# ReceiverPCB_trial1.net
KiCad netlist of a schematic drawn in EAGLE
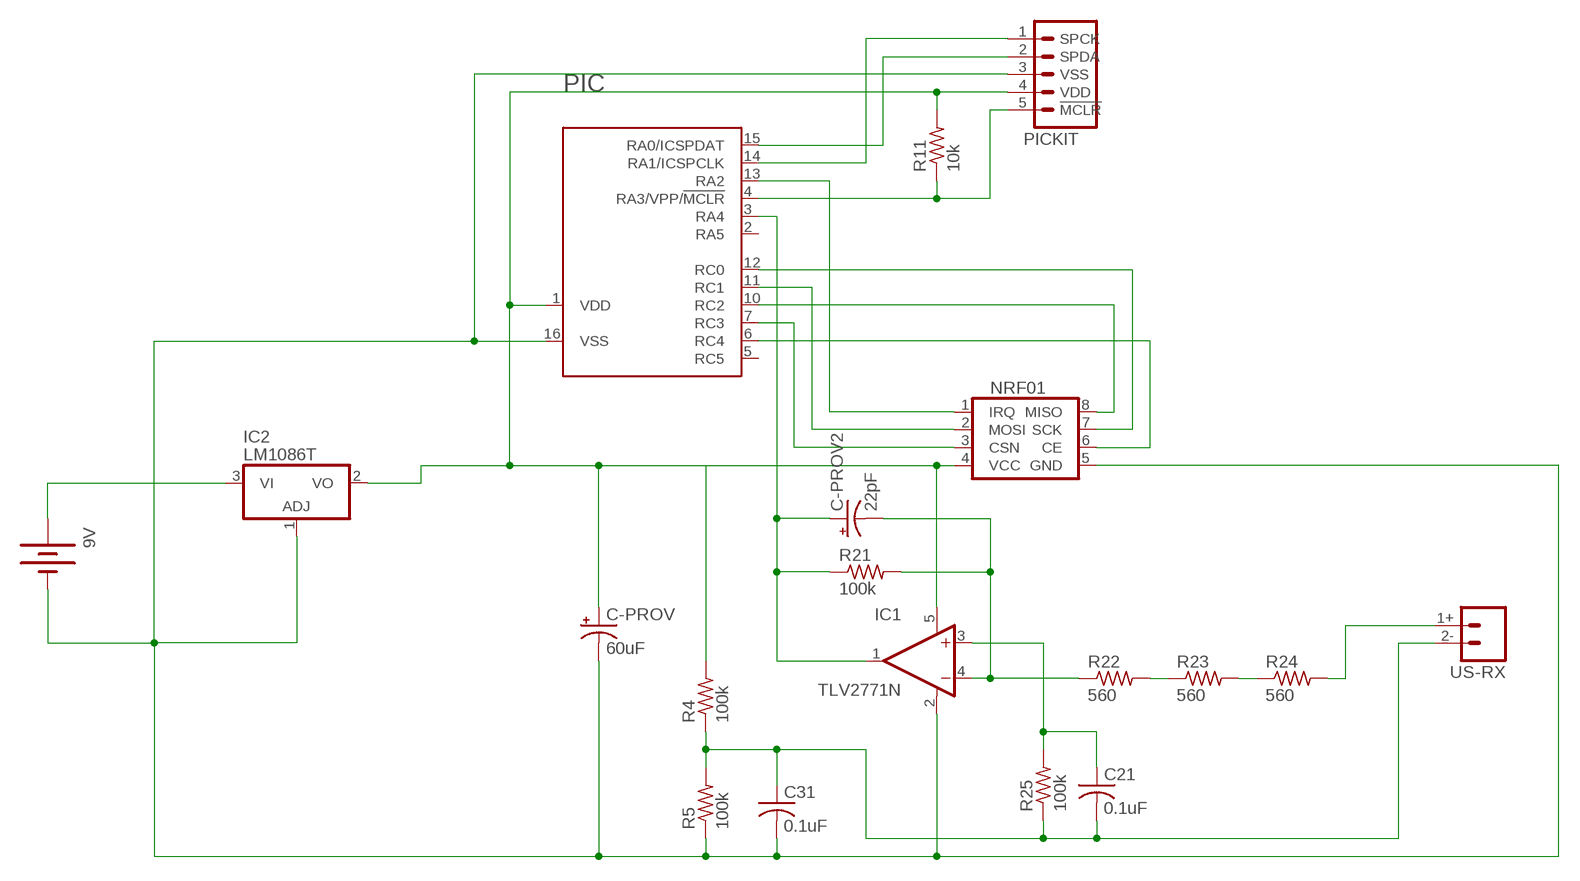
[diagram p0: schematic, sheet 1]

(export (version "E")
  (design (tool "Eeschema 10.0.6"))
  (components
    (comp (ref "9V")
      (value "BATTERY9V")
      (footprint "eagle-import:BATTCON_9V")
      (libsource (lib "eagle-import") (part "BATTERY9V"))
    )
    (comp (ref "C-PROV")
      (value "60uF")
      (footprint "eagle-import:E2,5-6E")
      (libsource (lib "eagle-import") (part "CPOL-USE2,5-6E"))
    )
    (comp (ref "C-PROV2")
      (value "22pF")
      (footprint "eagle-import:E2,5-6E")
      (libsource (lib "eagle-import") (part "CPOL-USE2,5-6E"))
    )
    (comp (ref "C21")
      (value "0.1uF")
      (footprint "eagle-import:C0805")
      (libsource (lib "eagle-import") (part "C-USC0805"))
    )
    (comp (ref "C31")
      (value "0.1uF")
      (footprint "eagle-import:C0805")
      (libsource (lib "eagle-import") (part "C-USC0805"))
    )
    (comp (ref "IC1")
      (value "TLV2771N")
      (footprint "eagle-import:SOT23-5")
      (fields (field (name "MF") "TEXAS INSTRUMENTS") (field (name "MPN") "OPA237NA/250"))
      (libsource (lib "eagle-import") (part "TLV2771N"))
    )
    (comp (ref "IC2")
      (value "LM1086T")
      (footprint "eagle-import:TO220H")
      (libsource (lib "eagle-import") (part "LM1086T"))
    )
    (comp (ref "NRF01")
      (value "NRF01")
      (footprint "eagle-import:JP4Q")
      (libsource (lib "eagle-import") (part "NRF01"))
    )
    (comp (ref "PIC")
      (value "PIC16F1503(DIL16)")
      (footprint "eagle-import:DIL16")
      (libsource (lib "eagle-import") (part "PIC16F1503(DIL16)"))
    )
    (comp (ref "PICKIT")
      (value "M05PTH")
      (footprint "eagle-import:1X05")
      (libsource (lib "eagle-import") (part "M05PTH"))
    )
    (comp (ref "R4")
      (value "100k")
      (footprint "eagle-import:R0805")
      (libsource (lib "eagle-import") (part "R-US_R0805"))
    )
    (comp (ref "R5")
      (value "100k")
      (footprint "eagle-import:R0805")
      (libsource (lib "eagle-import") (part "R-US_R0805"))
    )
    (comp (ref "R11")
      (value "10k")
      (footprint "eagle-import:R0805")
      (libsource (lib "eagle-import") (part "R-US_R0805"))
    )
    (comp (ref "R21")
      (value "100k")
      (footprint "eagle-import:R0805")
      (libsource (lib "eagle-import") (part "R-US_R0805"))
    )
    (comp (ref "R22")
      (value "560")
      (footprint "eagle-import:R0805")
      (libsource (lib "eagle-import") (part "R-US_R0805"))
    )
    (comp (ref "R23")
      (value "560")
      (footprint "eagle-import:R0805")
      (libsource (lib "eagle-import") (part "R-US_R0805"))
    )
    (comp (ref "R24")
      (value "560")
      (footprint "eagle-import:R0805")
      (libsource (lib "eagle-import") (part "R-US_R0805"))
    )
    (comp (ref "R25")
      (value "100k")
      (footprint "eagle-import:R0805")
      (libsource (lib "eagle-import") (part "R-US_R0805"))
    )
    (comp (ref "US-RX")
      (value "M02UT-1640K-TT-2-R")
      (footprint "eagle-import:ULTRASONIC-PEIZO")
      (libsource (lib "eagle-import") (part "M02UT-1640K-TT-2-R"))
    )
  )
  (nets
    (net (code "1") (name "Net-(IC1-+IN)") (class "Default")
      (node (ref "C21") (pin "1") (pinfunction "1_1") (pintype "passive"))
      (node (ref "IC1") (pin "3") (pinfunction "+IN_3") (pintype "input"))
      (node (ref "R25") (pin "2") (pinfunction "2_2") (pintype "passive"))
    )
    (net (code "2") (name "Net-(IC1--IN)") (class "Default")
      (node (ref "C-PROV2") (pin "-") (pinfunction "-_-") (pintype "passive"))
      (node (ref "IC1") (pin "4") (pinfunction "-IN_4") (pintype "input"))
      (node (ref "R21") (pin "2") (pinfunction "2_2") (pintype "passive"))
      (node (ref "R22") (pin "1") (pinfunction "1_1") (pintype "passive"))
    )
    (net (code "3") (name "Net-(IC1-OUT)") (class "Default")
      (node (ref "C-PROV2") (pin "+") (pinfunction "+_+") (pintype "passive"))
      (node (ref "IC1") (pin "1") (pinfunction "OUT_1") (pintype "output"))
      (node (ref "PIC") (pin "3") (pinfunction "RA4_3") (pintype "bidirectional"))
      (node (ref "R21") (pin "1") (pinfunction "1_1") (pintype "passive"))
    )
    (net (code "4") (name "Net-(IC1-V+)") (class "Default")
      (node (ref "C-PROV") (pin "+") (pinfunction "+_+") (pintype "passive"))
      (node (ref "IC1") (pin "5") (pinfunction "V+_5") (pintype "power_in"))
      (node (ref "IC2") (pin "2") (pinfunction "VO_2") (pintype "passive"))
      (node (ref "NRF01") (pin "4") (pinfunction "VCC_4") (pintype "passive"))
      (node (ref "PIC") (pin "1") (pinfunction "VDD_1") (pintype "bidirectional"))
      (node (ref "PICKIT") (pin "4") (pinfunction "VDD_4") (pintype "passive"))
      (node (ref "R11") (pin "2") (pinfunction "2_2") (pintype "passive"))
      (node (ref "R4") (pin "2") (pinfunction "2_2") (pintype "passive"))
    )
    (net (code "5") (name "Net-(IC1-V-)") (class "Default")
      (node (ref "9V") (pin "-") (pinfunction "-_-") (pintype "power_in"))
      (node (ref "C-PROV") (pin "-") (pinfunction "-_-") (pintype "passive"))
      (node (ref "C31") (pin "2") (pinfunction "2_2") (pintype "passive"))
      (node (ref "IC1") (pin "2") (pinfunction "V-_2") (pintype "power_in"))
      (node (ref "IC2") (pin "1") (pinfunction "ADJ_1") (pintype "input"))
      (node (ref "NRF01") (pin "5") (pinfunction "GND_5") (pintype "passive"))
      (node (ref "PIC") (pin "16") (pinfunction "VSS_16") (pintype "bidirectional"))
      (node (ref "PICKIT") (pin "3") (pinfunction "VSS_3") (pintype "passive"))
      (node (ref "R5") (pin "1") (pinfunction "1_1") (pintype "passive"))
    )
    (net (code "6") (name "Net-(IC2-VI)") (class "Default")
      (node (ref "9V") (pin "+") (pinfunction "+_+") (pintype "power_in"))
      (node (ref "IC2") (pin "3") (pinfunction "VI_3") (pintype "input"))
    )
    (net (code "7") (name "Net-(NRF01-CE)") (class "Default")
      (node (ref "NRF01") (pin "6") (pinfunction "CE_6") (pintype "passive"))
      (node (ref "PIC") (pin "6") (pinfunction "RC4_6") (pintype "bidirectional"))
    )
    (net (code "8") (name "Net-(NRF01-CSN)") (class "Default")
      (node (ref "NRF01") (pin "3") (pinfunction "CSN_3") (pintype "passive"))
      (node (ref "PIC") (pin "7") (pinfunction "RC3_7") (pintype "bidirectional"))
    )
    (net (code "9") (name "Net-(NRF01-IRQ)") (class "Default")
      (node (ref "NRF01") (pin "1") (pinfunction "IRQ_1") (pintype "passive"))
      (node (ref "PIC") (pin "13") (pinfunction "RA2_13") (pintype "bidirectional"))
    )
    (net (code "10") (name "Net-(NRF01-MISO)") (class "Default")
      (node (ref "NRF01") (pin "8") (pinfunction "MISO_8") (pintype "passive"))
      (node (ref "PIC") (pin "10") (pinfunction "RC2_10") (pintype "bidirectional"))
    )
    (net (code "11") (name "Net-(NRF01-MOSI)") (class "Default")
      (node (ref "NRF01") (pin "2") (pinfunction "MOSI_2") (pintype "passive"))
      (node (ref "PIC") (pin "11") (pinfunction "RC1_11") (pintype "bidirectional"))
    )
    (net (code "12") (name "Net-(NRF01-SCK)") (class "Default")
      (node (ref "NRF01") (pin "7") (pinfunction "SCK_7") (pintype "passive"))
      (node (ref "PIC") (pin "12") (pinfunction "RC0_12") (pintype "bidirectional"))
    )
    (net (code "13") (name "Net-(PIC-RA0{slash}ICSPDAT)") (class "Default")
      (node (ref "PIC") (pin "15") (pinfunction "RA0/ICSPDAT_15") (pintype "bidirectional"))
      (node (ref "PICKIT") (pin "2") (pinfunction "SPDA_2") (pintype "passive"))
    )
    (net (code "14") (name "Net-(PIC-RA1{slash}ICSPCLK)") (class "Default")
      (node (ref "PIC") (pin "14") (pinfunction "RA1/ICSPCLK_14") (pintype "bidirectional"))
      (node (ref "PICKIT") (pin "1") (pinfunction "SPCK_1") (pintype "passive"))
    )
    (net (code "15") (name "Net-(PIC-RA3{slash}VPP{slash}~{MCLR})") (class "Default")
      (node (ref "PIC") (pin "4") (pinfunction "RA3/VPP/~{MCLR}_4") (pintype "bidirectional"))
      (node (ref "PICKIT") (pin "5") (pinfunction "~{MCLR}_5") (pintype "passive"))
      (node (ref "R11") (pin "1") (pinfunction "1_1") (pintype "passive"))
    )
    (net (code "16") (name "Net-(R22-Pad2)") (class "Default")
      (node (ref "R22") (pin "2") (pinfunction "2_2") (pintype "passive"))
      (node (ref "R23") (pin "1") (pinfunction "1_1") (pintype "passive"))
    )
    (net (code "17") (name "Net-(R23-Pad2)") (class "Default")
      (node (ref "R23") (pin "2") (pinfunction "2_2") (pintype "passive"))
      (node (ref "R24") (pin "1") (pinfunction "1_1") (pintype "passive"))
    )
    (net (code "18") (name "Net-(US-RX-1)") (class "Default")
      (node (ref "R24") (pin "2") (pinfunction "2_2") (pintype "passive"))
      (node (ref "US-RX") (pin "1+") (pinfunction "1_1+") (pintype "passive"))
    )
    (net (code "19") (name "Net-(US-RX-2)") (class "Default")
      (node (ref "C21") (pin "2") (pinfunction "2_2") (pintype "passive"))
      (node (ref "C31") (pin "1") (pinfunction "1_1") (pintype "passive"))
      (node (ref "R25") (pin "1") (pinfunction "1_1") (pintype "passive"))
      (node (ref "R4") (pin "1") (pinfunction "1_1") (pintype "passive"))
      (node (ref "R5") (pin "2") (pinfunction "2_2") (pintype "passive"))
      (node (ref "US-RX") (pin "2-") (pinfunction "2_2-") (pintype "passive"))
    )
    (net (code "20") (name "unconnected-(PIC-RA5-Pad2)") (class "Default")
      (node (ref "PIC") (pin "2") (pinfunction "RA5_2") (pintype "bidirectional"))
    )
    (net (code "21") (name "unconnected-(PIC-RC5-Pad5)") (class "Default")
      (node (ref "PIC") (pin "5") (pinfunction "RC5_5") (pintype "bidirectional"))
    )
  )
)
